# DMA.net
KiCad netlist of a schematic drawn in Altium Designer
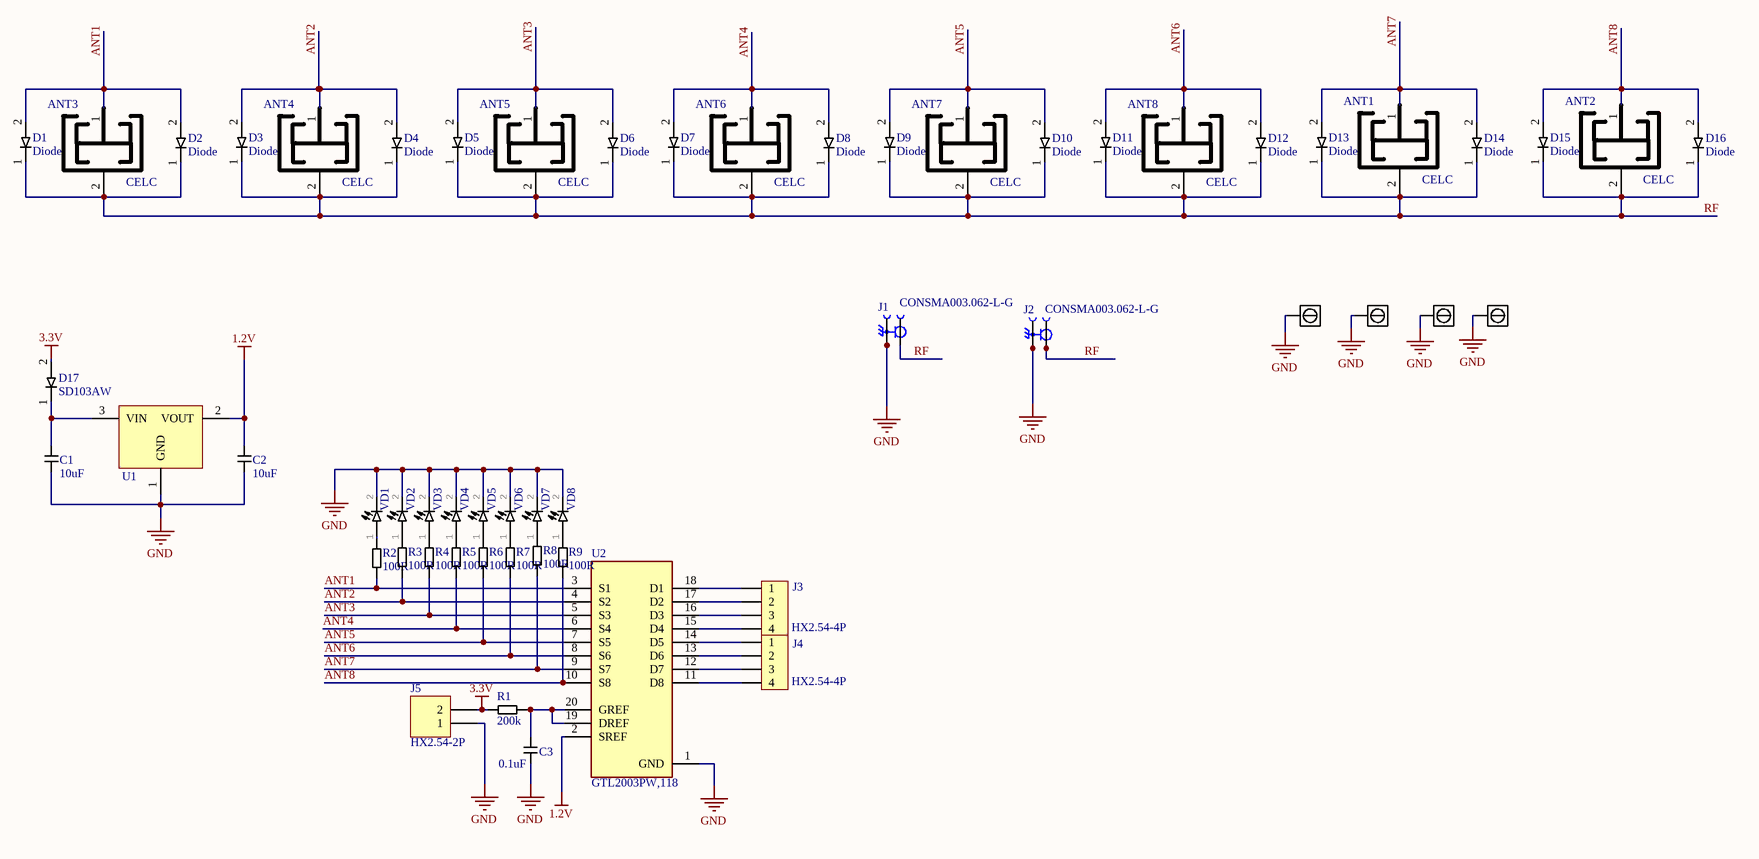
[diagram p0: DMA.SchDoc]

(export (version "E")
  (design (tool "Eeschema 10.0.6"))
  (components
    (comp (ref "1")
      (value "SMTSO_STAND_M3")
      (footprint "M3x1")
      (libsource (lib "SMTSO") (part "SMTSO_STAND_M3"))
    )
    (comp (ref "2")
      (value "SMTSO_STAND_M3")
      (footprint "M3x1")
      (libsource (lib "SMTSO") (part "SMTSO_STAND_M3"))
    )
    (comp (ref "3")
      (value "SMTSO_STAND_M3")
      (footprint "M3x1")
      (libsource (lib "SMTSO") (part "SMTSO_STAND_M3"))
    )
    (comp (ref "4")
      (value "SMTSO_STAND_M3")
      (footprint "M3x1")
      (libsource (lib "SMTSO") (part "SMTSO_STAND_M3"))
    )
    (comp (ref "ANT1") (value "CELC") (footprint "PCBComponent_1") (libsource (lib "CELC") (part "CELC")))
    (comp (ref "ANT2") (value "CELC") (footprint "PCBComponent_1") (libsource (lib "CELC") (part "CELC")))
    (comp (ref "ANT3") (value "CELC") (footprint "PCBComponent_1") (libsource (lib "CELC") (part "CELC")))
    (comp (ref "ANT4") (value "CELC") (footprint "PCBComponent_1") (libsource (lib "CELC") (part "CELC")))
    (comp (ref "ANT5") (value "CELC") (footprint "PCBComponent_1") (libsource (lib "CELC") (part "CELC")))
    (comp (ref "ANT6") (value "CELC") (footprint "PCBComponent_1") (libsource (lib "CELC") (part "CELC")))
    (comp (ref "ANT7") (value "CELC") (footprint "PCBComponent_1") (libsource (lib "CELC") (part "CELC")))
    (comp (ref "ANT8") (value "CELC") (footprint "PCBComponent_1") (libsource (lib "CELC") (part "CELC")))
    (comp (ref "C1")
      (value "10uF")
      (footprint "0603_MD_CAPC1608X04N")
      (description "Capacitors IPC")
      (libsource (lib "Passive") (part "C"))
    )
    (comp (ref "C2")
      (value "10uF")
      (footprint "0603_MD_CAPC1608X04N")
      (description "Capacitors IPC")
      (libsource (lib "Passive") (part "C"))
    )
    (comp (ref "C3")
      (value "0.1uF")
      (footprint "0603_MD_CAPC1608X04N")
      (description "Capacitors IPC")
      (libsource (lib "Passive") (part "C"))
    )
    (comp (ref "D1")
      (value "Diode")
      (footprint "SOD123_MD_DIOM2615X12N")
      (description "SMD diode")
      (libsource (lib "Diodes") (part "Diode"))
    )
    (comp (ref "D2")
      (value "Diode")
      (footprint "SOD123_MD_DIOM2615X12N")
      (description "SMD diode")
      (libsource (lib "Diodes") (part "Diode"))
    )
    (comp (ref "D3")
      (value "Diode")
      (footprint "SOD123_MD_DIOM2615X12N")
      (description "SMD diode")
      (libsource (lib "Diodes") (part "Diode"))
    )
    (comp (ref "D4")
      (value "Diode")
      (footprint "SOD123_MD_DIOM2615X12N")
      (description "SMD diode")
      (libsource (lib "Diodes") (part "Diode"))
    )
    (comp (ref "D5")
      (value "Diode")
      (footprint "SOD123_MD_DIOM2615X12N")
      (description "SMD diode")
      (libsource (lib "Diodes") (part "Diode"))
    )
    (comp (ref "D6")
      (value "Diode")
      (footprint "SOD123_MD_DIOM2615X12N")
      (description "SMD diode")
      (libsource (lib "Diodes") (part "Diode"))
    )
    (comp (ref "D7")
      (value "Diode")
      (footprint "SOD123_MD_DIOM2615X12N")
      (description "SMD diode")
      (libsource (lib "Diodes") (part "Diode"))
    )
    (comp (ref "D8")
      (value "Diode")
      (footprint "SOD123_MD_DIOM2615X12N")
      (description "SMD diode")
      (libsource (lib "Diodes") (part "Diode"))
    )
    (comp (ref "D9")
      (value "Diode")
      (footprint "SOD123_MD_DIOM2615X12N")
      (description "SMD diode")
      (libsource (lib "Diodes") (part "Diode"))
    )
    (comp (ref "D10")
      (value "Diode")
      (footprint "SOD123_MD_DIOM2615X12N")
      (description "SMD diode")
      (libsource (lib "Diodes") (part "Diode"))
    )
    (comp (ref "D11")
      (value "Diode")
      (footprint "SOD123_MD_DIOM2615X12N")
      (description "SMD diode")
      (libsource (lib "Diodes") (part "Diode"))
    )
    (comp (ref "D12")
      (value "Diode")
      (footprint "SOD123_MD_DIOM2615X12N")
      (description "SMD diode")
      (libsource (lib "Diodes") (part "Diode"))
    )
    (comp (ref "D13")
      (value "Diode")
      (footprint "SOD123_MD_DIOM2615X12N")
      (description "SMD diode")
      (libsource (lib "Diodes") (part "Diode"))
    )
    (comp (ref "D14")
      (value "Diode")
      (footprint "SOD123_MD_DIOM2615X12N")
      (description "SMD diode")
      (libsource (lib "Diodes") (part "Diode"))
    )
    (comp (ref "D15")
      (value "Diode")
      (footprint "SOD123_MD_DIOM2615X12N")
      (description "SMD diode")
      (libsource (lib "Diodes") (part "Diode"))
    )
    (comp (ref "D16")
      (value "Diode")
      (footprint "SOD123_MD_DIOM2615X12N")
      (description "SMD diode")
      (libsource (lib "Diodes") (part "Diode"))
    )
    (comp (ref "D17")
      (value "SD103AW")
      (footprint "SOD123_MD_DIOM2615X12N")
      (description "SMD diode")
      (libsource (lib "Diodes") (part "Diode"))
    )
    (comp (ref "J1")
      (value "CONSMA003.062-L-G")
      (footprint "TE_CONSMA003.062-L-G")
      (libsource (lib "CONSMA003.062-L-G") (part "CONSMA003.062-L-G"))
    )
    (comp (ref "J2")
      (value "CONSMA003.062-L-G")
      (footprint "TE_CONSMA003.062-L-G")
      (libsource (lib "CONSMA003.062-L-G") (part "CONSMA003.062-L-G"))
    )
    (comp (ref "J3")
      (value "HX2.54-4P")
      (footprint "JST_S4B-XH-A(LF)(SN)")
      (description "JST HX 2.54 4P")
      (libsource (lib "Connector") (part "HX2.54-4P"))
    )
    (comp (ref "J4")
      (value "HX2.54-4P")
      (footprint "JST_S4B-XH-A(LF)(SN)")
      (description "JST HX 2.54 4P")
      (libsource (lib "Connector") (part "HX2.54-4P"))
    )
    (comp (ref "J5")
      (value "HX2.54-2P")
      (footprint "JST_S2B-XH-A(LF)(SN)")
      (description "JST HX 2.54 2P")
      (libsource (lib "Connector") (part "HX2.54-2P"))
    )
    (comp (ref "R1")
      (value "200k")
      (footprint "0805_MD_RESC2012X06N")
      (description "Resistors IPC")
      (libsource (lib "Passive") (part "R"))
    )
    (comp (ref "R2")
      (value "100R")
      (footprint "0805_MD_RESC2012X06N")
      (description "Resistors IPC")
      (libsource (lib "Passive") (part "R"))
    )
    (comp (ref "R3")
      (value "100R")
      (footprint "0805_MD_RESC2012X06N")
      (description "Resistors IPC")
      (libsource (lib "Passive") (part "R"))
    )
    (comp (ref "R4")
      (value "100R")
      (footprint "0805_MD_RESC2012X06N")
      (description "Resistors IPC")
      (libsource (lib "Passive") (part "R"))
    )
    (comp (ref "R5")
      (value "100R")
      (footprint "0805_MD_RESC2012X06N")
      (description "Resistors IPC")
      (libsource (lib "Passive") (part "R"))
    )
    (comp (ref "R6")
      (value "100R")
      (footprint "0805_MD_RESC2012X06N")
      (description "Resistors IPC")
      (libsource (lib "Passive") (part "R"))
    )
    (comp (ref "R7")
      (value "100R")
      (footprint "0805_MD_RESC2012X06N")
      (description "Resistors IPC")
      (libsource (lib "Passive") (part "R"))
    )
    (comp (ref "R8")
      (value "100R")
      (footprint "0805_MD_RESC2012X06N")
      (description "Resistors IPC")
      (libsource (lib "Passive") (part "R"))
    )
    (comp (ref "R9")
      (value "100R")
      (footprint "0805_MD_RESC2012X06N")
      (description "Resistors IPC")
      (libsource (lib "Passive") (part "R"))
    )
    (comp (ref "U1")
      (value "AMS1117-3.3")
      (footprint "SOT223_3_HD_SOT230P700X180-4L")
      (description "800mA LOW DROPOUT VOLTAGE REGULATOR")
      (libsource (lib "LDO") (part "AMS1117-3.3"))
    )
    (comp (ref "U2")
      (value "GTL2003PW,118")
      (footprint "SOP65P640X110-20N")
      (description "Voltage Level Translator Bidirectional 1 Circuit 8 Channel 20-TSSOP")
      (fields (field (name "DIGI-KEY_PART_NUMBER") "568-12295-1-ND") (field (name "MF") "NXP USA"))
      (libsource (lib "GTL2003PW_118") (part "GTL2003PW,118"))
    )
    (comp (ref "VD1") (value "LED") (footprint "D0805") (libsource (lib "Diodes") (part "LED")))
    (comp (ref "VD2") (value "LED") (footprint "D0805") (libsource (lib "Diodes") (part "LED")))
    (comp (ref "VD3") (value "LED") (footprint "D0805") (libsource (lib "Diodes") (part "LED")))
    (comp (ref "VD4") (value "LED") (footprint "D0805") (libsource (lib "Diodes") (part "LED")))
    (comp (ref "VD5") (value "LED") (footprint "D0805") (libsource (lib "Diodes") (part "LED")))
    (comp (ref "VD6") (value "LED") (footprint "D0805") (libsource (lib "Diodes") (part "LED")))
    (comp (ref "VD7") (value "LED") (footprint "D0805") (libsource (lib "Diodes") (part "LED")))
    (comp (ref "VD8") (value "LED") (footprint "D0805") (libsource (lib "Diodes") (part "LED")))
  )
  (nets
    (net (code "1") (name "/ANT1") (class "Default")
      (node (ref "ANT3") (pin "1") (pinfunction "RF_1") (pintype "passive"))
      (node (ref "D1") (pin "2") (pinfunction "A_2") (pintype "passive"))
      (node (ref "D2") (pin "2") (pinfunction "A_2") (pintype "passive"))
      (node (ref "R2") (pin "1") (pinfunction "1_1") (pintype "passive"))
      (node (ref "U2") (pin "3") (pinfunction "S1_3") (pintype "passive"))
    )
    (net (code "2") (name "/ANT2") (class "Default")
      (node (ref "ANT4") (pin "1") (pinfunction "RF_1") (pintype "passive"))
      (node (ref "D3") (pin "2") (pinfunction "A_2") (pintype "passive"))
      (node (ref "D4") (pin "2") (pinfunction "A_2") (pintype "passive"))
      (node (ref "R3") (pin "1") (pinfunction "1_1") (pintype "passive"))
      (node (ref "U2") (pin "4") (pinfunction "S2_4") (pintype "passive"))
    )
    (net (code "3") (name "/ANT3") (class "Default")
      (node (ref "ANT5") (pin "1") (pinfunction "RF_1") (pintype "passive"))
      (node (ref "D5") (pin "2") (pinfunction "A_2") (pintype "passive"))
      (node (ref "D6") (pin "2") (pinfunction "A_2") (pintype "passive"))
      (node (ref "R4") (pin "1") (pinfunction "1_1") (pintype "passive"))
      (node (ref "U2") (pin "5") (pinfunction "S3_5") (pintype "passive"))
    )
    (net (code "4") (name "/ANT4") (class "Default")
      (node (ref "ANT6") (pin "1") (pinfunction "RF_1") (pintype "passive"))
      (node (ref "D7") (pin "2") (pinfunction "A_2") (pintype "passive"))
      (node (ref "D8") (pin "2") (pinfunction "A_2") (pintype "passive"))
      (node (ref "R5") (pin "1") (pinfunction "1_1") (pintype "passive"))
      (node (ref "U2") (pin "6") (pinfunction "S4_6") (pintype "passive"))
    )
    (net (code "5") (name "/ANT5") (class "Default")
      (node (ref "ANT7") (pin "1") (pinfunction "RF_1") (pintype "passive"))
      (node (ref "D10") (pin "2") (pinfunction "A_2") (pintype "passive"))
      (node (ref "D9") (pin "2") (pinfunction "A_2") (pintype "passive"))
      (node (ref "R6") (pin "1") (pinfunction "1_1") (pintype "passive"))
      (node (ref "U2") (pin "7") (pinfunction "S5_7") (pintype "passive"))
    )
    (net (code "6") (name "/ANT6") (class "Default")
      (node (ref "ANT8") (pin "1") (pinfunction "RF_1") (pintype "passive"))
      (node (ref "D11") (pin "2") (pinfunction "A_2") (pintype "passive"))
      (node (ref "D12") (pin "2") (pinfunction "A_2") (pintype "passive"))
      (node (ref "R7") (pin "1") (pinfunction "1_1") (pintype "passive"))
      (node (ref "U2") (pin "8") (pinfunction "S6_8") (pintype "passive"))
    )
    (net (code "7") (name "/ANT7") (class "Default")
      (node (ref "ANT1") (pin "1") (pinfunction "RF_1") (pintype "passive"))
      (node (ref "D13") (pin "2") (pinfunction "A_2") (pintype "passive"))
      (node (ref "D14") (pin "2") (pinfunction "A_2") (pintype "passive"))
      (node (ref "R8") (pin "1") (pinfunction "1_1") (pintype "passive"))
      (node (ref "U2") (pin "9") (pinfunction "S7_9") (pintype "passive"))
    )
    (net (code "8") (name "/ANT8") (class "Default")
      (node (ref "ANT2") (pin "1") (pinfunction "RF_1") (pintype "passive"))
      (node (ref "D15") (pin "2") (pinfunction "A_2") (pintype "passive"))
      (node (ref "D16") (pin "2") (pinfunction "A_2") (pintype "passive"))
      (node (ref "R9") (pin "1") (pinfunction "1_1") (pintype "passive"))
      (node (ref "U2") (pin "10") (pinfunction "S8_10") (pintype "passive"))
    )
    (net (code "9") (name "/RF") (class "Default")
      (node (ref "ANT1") (pin "2") (pinfunction "GND_2") (pintype "passive"))
      (node (ref "ANT2") (pin "2") (pinfunction "GND_2") (pintype "passive"))
      (node (ref "ANT3") (pin "2") (pinfunction "GND_2") (pintype "passive"))
      (node (ref "ANT4") (pin "2") (pinfunction "GND_2") (pintype "passive"))
      (node (ref "ANT5") (pin "2") (pinfunction "GND_2") (pintype "passive"))
      (node (ref "ANT6") (pin "2") (pinfunction "GND_2") (pintype "passive"))
      (node (ref "ANT7") (pin "2") (pinfunction "GND_2") (pintype "passive"))
      (node (ref "ANT8") (pin "2") (pinfunction "GND_2") (pintype "passive"))
      (node (ref "D1") (pin "1") (pinfunction "C_1") (pintype "passive"))
      (node (ref "D10") (pin "1") (pinfunction "C_1") (pintype "passive"))
      (node (ref "D11") (pin "1") (pinfunction "C_1") (pintype "passive"))
      (node (ref "D12") (pin "1") (pinfunction "C_1") (pintype "passive"))
      (node (ref "D13") (pin "1") (pinfunction "C_1") (pintype "passive"))
      (node (ref "D14") (pin "1") (pinfunction "C_1") (pintype "passive"))
      (node (ref "D15") (pin "1") (pinfunction "C_1") (pintype "passive"))
      (node (ref "D16") (pin "1") (pinfunction "C_1") (pintype "passive"))
      (node (ref "D2") (pin "1") (pinfunction "C_1") (pintype "passive"))
      (node (ref "D3") (pin "1") (pinfunction "C_1") (pintype "passive"))
      (node (ref "D4") (pin "1") (pinfunction "C_1") (pintype "passive"))
      (node (ref "D5") (pin "1") (pinfunction "C_1") (pintype "passive"))
      (node (ref "D6") (pin "1") (pinfunction "C_1") (pintype "passive"))
      (node (ref "D7") (pin "1") (pinfunction "C_1") (pintype "passive"))
      (node (ref "D8") (pin "1") (pinfunction "C_1") (pintype "passive"))
      (node (ref "D9") (pin "1") (pinfunction "C_1") (pintype "passive"))
      (node (ref "J1") (pin "1") (pinfunction "SIG_1") (pintype "passive"))
      (node (ref "J2") (pin "1") (pinfunction "SIG_1") (pintype "passive"))
    )
    (net (code "10") (name "1.2V") (class "Default")
      (node (ref "C2") (pin "1") (pinfunction "1_1") (pintype "passive"))
      (node (ref "U1") (pin "2") (pinfunction "VOUT_2") (pintype "passive"))
      (node (ref "U2") (pin "2") (pinfunction "SREF_2") (pintype "passive"))
    )
    (net (code "11") (name "3.3V") (class "Default")
      (node (ref "D17") (pin "2") (pinfunction "A_2") (pintype "passive"))
      (node (ref "J5") (pin "2") (pinfunction "2_2") (pintype "passive"))
      (node (ref "R1") (pin "1") (pinfunction "1_1") (pintype "passive"))
    )
    (net (code "12") (name "GND") (class "Default")
      (node (ref "1") (pin "1") (pinfunction "1_1") (pintype "passive"))
      (node (ref "2") (pin "1") (pinfunction "1_1") (pintype "passive"))
      (node (ref "3") (pin "1") (pinfunction "1_1") (pintype "passive"))
      (node (ref "4") (pin "1") (pinfunction "1_1") (pintype "passive"))
      (node (ref "C1") (pin "2") (pinfunction "2_2") (pintype "passive"))
      (node (ref "C2") (pin "2") (pinfunction "2_2") (pintype "passive"))
      (node (ref "C3") (pin "2") (pinfunction "2_2") (pintype "passive"))
      (node (ref "J1") (pin "2") (pinfunction "SH_2") (pintype "power_in"))
      (node (ref "J1") (pin "3") (pinfunction "SH_3") (pintype "power_in"))
      (node (ref "J1") (pin "4") (pinfunction "SH_4") (pintype "power_in"))
      (node (ref "J1") (pin "5") (pinfunction "SH_5") (pintype "power_in"))
      (node (ref "J2") (pin "2") (pinfunction "SH_2") (pintype "power_in"))
      (node (ref "J2") (pin "3") (pinfunction "SH_3") (pintype "power_in"))
      (node (ref "J2") (pin "4") (pinfunction "SH_4") (pintype "power_in"))
      (node (ref "J2") (pin "5") (pinfunction "SH_5") (pintype "power_in"))
      (node (ref "J5") (pin "1") (pinfunction "1_1") (pintype "passive"))
      (node (ref "U1") (pin "1") (pinfunction "GND_1") (pintype "passive"))
      (node (ref "U2") (pin "1") (pinfunction "GND_1") (pintype "power_in"))
      (node (ref "VD1") (pin "2") (pinfunction "C_2") (pintype "passive"))
      (node (ref "VD2") (pin "2") (pinfunction "C_2") (pintype "passive"))
      (node (ref "VD3") (pin "2") (pinfunction "C_2") (pintype "passive"))
      (node (ref "VD4") (pin "2") (pinfunction "C_2") (pintype "passive"))
      (node (ref "VD5") (pin "2") (pinfunction "C_2") (pintype "passive"))
      (node (ref "VD6") (pin "2") (pinfunction "C_2") (pintype "passive"))
      (node (ref "VD7") (pin "2") (pinfunction "C_2") (pintype "passive"))
      (node (ref "VD8") (pin "2") (pinfunction "C_2") (pintype "passive"))
    )
    (net (code "13") (name "Net-(D17-C)") (class "Default")
      (node (ref "C1") (pin "1") (pinfunction "1_1") (pintype "passive"))
      (node (ref "D17") (pin "1") (pinfunction "C_1") (pintype "passive"))
      (node (ref "U1") (pin "3") (pinfunction "VIN_3") (pintype "passive"))
    )
    (net (code "14") (name "Net-(U2-D1)") (class "Default")
      (node (ref "J3") (pin "1") (pinfunction "1_1") (pintype "passive"))
      (node (ref "U2") (pin "18") (pinfunction "D1_18") (pintype "passive"))
    )
    (net (code "15") (name "Net-(U2-D2)") (class "Default")
      (node (ref "J3") (pin "2") (pinfunction "2_2") (pintype "passive"))
      (node (ref "U2") (pin "17") (pinfunction "D2_17") (pintype "passive"))
    )
    (net (code "16") (name "Net-(U2-D3)") (class "Default")
      (node (ref "J3") (pin "3") (pinfunction "3_3") (pintype "passive"))
      (node (ref "U2") (pin "16") (pinfunction "D3_16") (pintype "passive"))
    )
    (net (code "17") (name "Net-(U2-D4)") (class "Default")
      (node (ref "J3") (pin "4") (pinfunction "4_4") (pintype "passive"))
      (node (ref "U2") (pin "15") (pinfunction "D4_15") (pintype "passive"))
    )
    (net (code "18") (name "Net-(U2-D5)") (class "Default")
      (node (ref "J4") (pin "1") (pinfunction "1_1") (pintype "passive"))
      (node (ref "U2") (pin "14") (pinfunction "D5_14") (pintype "passive"))
    )
    (net (code "19") (name "Net-(U2-D6)") (class "Default")
      (node (ref "J4") (pin "2") (pinfunction "2_2") (pintype "passive"))
      (node (ref "U2") (pin "13") (pinfunction "D6_13") (pintype "passive"))
    )
    (net (code "20") (name "Net-(U2-D7)") (class "Default")
      (node (ref "J4") (pin "3") (pinfunction "3_3") (pintype "passive"))
      (node (ref "U2") (pin "12") (pinfunction "D7_12") (pintype "passive"))
    )
    (net (code "21") (name "Net-(U2-D8)") (class "Default")
      (node (ref "J4") (pin "4") (pinfunction "4_4") (pintype "passive"))
      (node (ref "U2") (pin "11") (pinfunction "D8_11") (pintype "passive"))
    )
    (net (code "22") (name "Net-(U2-DREF)") (class "Default")
      (node (ref "C3") (pin "1") (pinfunction "1_1") (pintype "passive"))
      (node (ref "R1") (pin "2") (pinfunction "2_2") (pintype "passive"))
      (node (ref "U2") (pin "19") (pinfunction "DREF_19") (pintype "passive"))
      (node (ref "U2") (pin "20") (pinfunction "GREF_20") (pintype "passive"))
    )
    (net (code "23") (name "Net-(VD1-A)") (class "Default")
      (node (ref "R2") (pin "2") (pinfunction "2_2") (pintype "passive"))
      (node (ref "VD1") (pin "1") (pinfunction "A_1") (pintype "passive"))
    )
    (net (code "24") (name "Net-(VD2-A)") (class "Default")
      (node (ref "R3") (pin "2") (pinfunction "2_2") (pintype "passive"))
      (node (ref "VD2") (pin "1") (pinfunction "A_1") (pintype "passive"))
    )
    (net (code "25") (name "Net-(VD3-A)") (class "Default")
      (node (ref "R4") (pin "2") (pinfunction "2_2") (pintype "passive"))
      (node (ref "VD3") (pin "1") (pinfunction "A_1") (pintype "passive"))
    )
    (net (code "26") (name "Net-(VD4-A)") (class "Default")
      (node (ref "R5") (pin "2") (pinfunction "2_2") (pintype "passive"))
      (node (ref "VD4") (pin "1") (pinfunction "A_1") (pintype "passive"))
    )
    (net (code "27") (name "Net-(VD5-A)") (class "Default")
      (node (ref "R6") (pin "2") (pinfunction "2_2") (pintype "passive"))
      (node (ref "VD5") (pin "1") (pinfunction "A_1") (pintype "passive"))
    )
    (net (code "28") (name "Net-(VD6-A)") (class "Default")
      (node (ref "R7") (pin "2") (pinfunction "2_2") (pintype "passive"))
      (node (ref "VD6") (pin "1") (pinfunction "A_1") (pintype "passive"))
    )
    (net (code "29") (name "Net-(VD7-A)") (class "Default")
      (node (ref "R8") (pin "2") (pinfunction "2_2") (pintype "passive"))
      (node (ref "VD7") (pin "1") (pinfunction "A_1") (pintype "passive"))
    )
    (net (code "30") (name "Net-(VD8-A)") (class "Default")
      (node (ref "R9") (pin "2") (pinfunction "2_2") (pintype "passive"))
      (node (ref "VD8") (pin "1") (pinfunction "A_1") (pintype "passive"))
    )
  )
)
